# MicroCurrent.net
KiCad netlist of a schematic drawn in Altium Designer
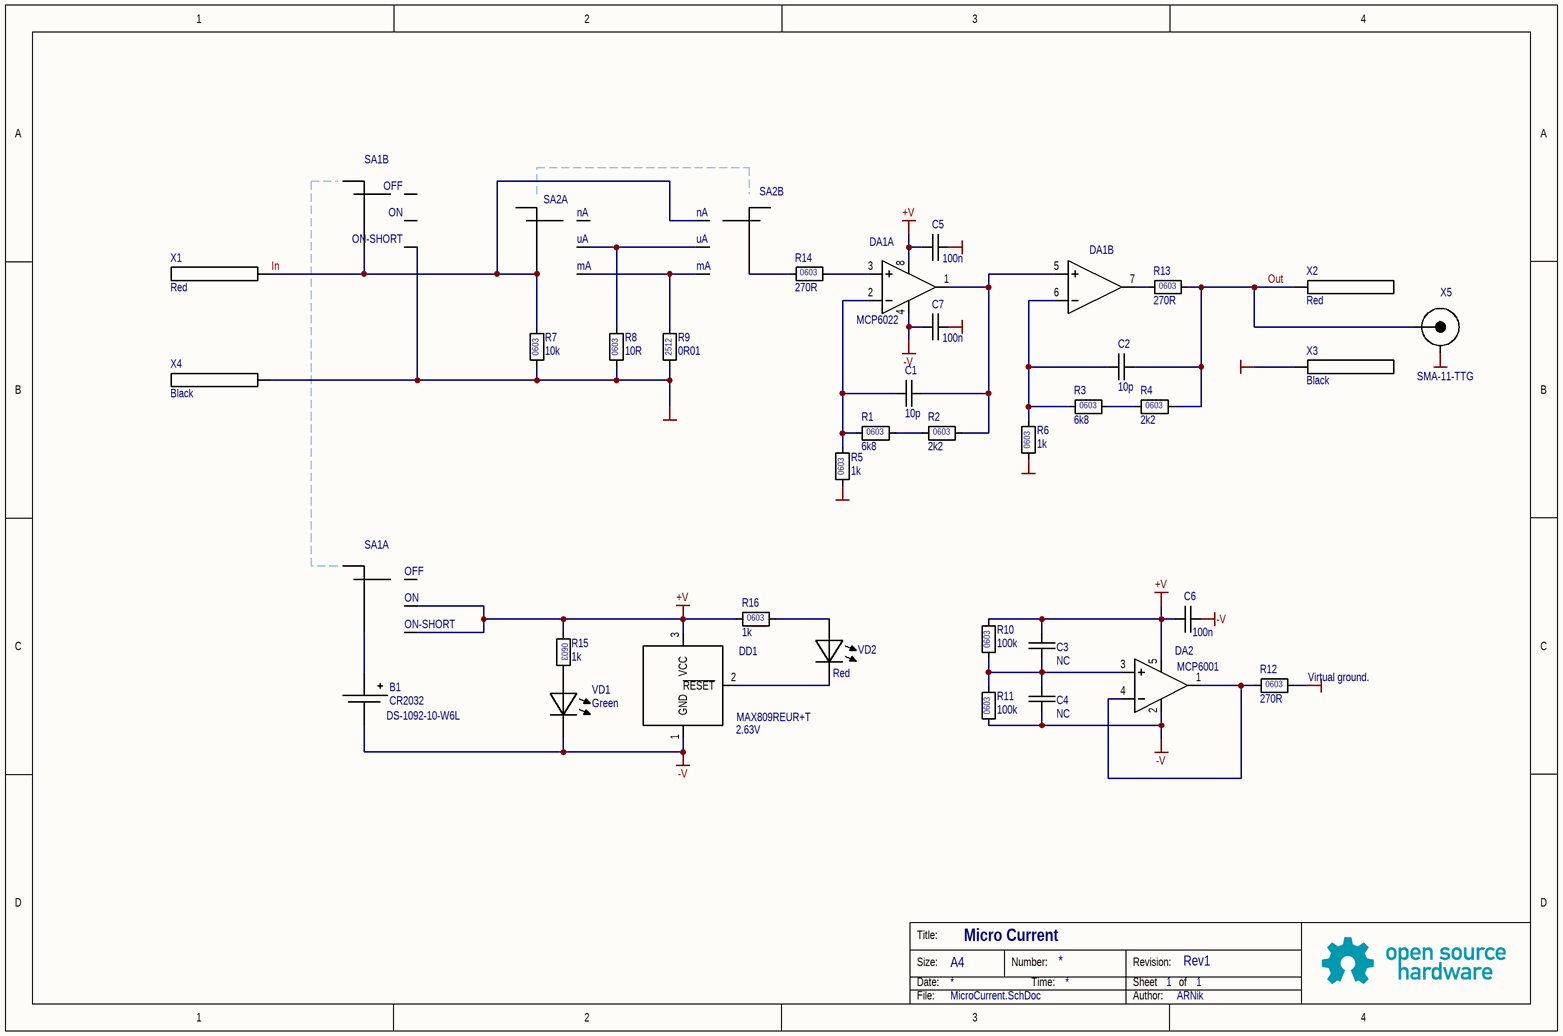
[diagram p0: MicroCurrent.SchDoc]

(export (version "E")
  (design (tool "Eeschema 10.0.6"))
  (components
    (comp (ref "B1")
      (value "CR2032")
      (footprint "DS1092-10-W6L")
      (description "CR2032 SMD battery holder")
      (fields (field (name "PART NUMBER") "DS-1092-10-W6L"))
      (libsource (lib "altium") (part "DS1092-10-W6L"))
    )
    (comp (ref "C1")
      (value "10p")
      (footprint "C0603")
      (description "Commercial Grade Mid Voltage (100 to 630V) ceramic capacitor")
      (fields (field (name "PART NUMBER") "C1608C0G2A100D080AA") (field (name "VOLTAGE") "100V"))
      (libsource (lib "altium") (part "Capacitor"))
    )
    (comp (ref "C2")
      (value "10p")
      (footprint "C0603")
      (description "Commercial Grade Mid Voltage (100 to 630V) ceramic capacitor")
      (fields (field (name "PART NUMBER") "C1608C0G2A100D080AA") (field (name "VOLTAGE") "100V"))
      (libsource (lib "altium") (part "Capacitor"))
    )
    (comp (ref "C3")
      (value "NC")
      (footprint "C0603")
      (description "NC 0603 Capasitor")
      (libsource (lib "altium") (part "Capacitor NB"))
    )
    (comp (ref "C4")
      (value "NC")
      (footprint "C0603")
      (description "NC 0603 Capasitor")
      (libsource (lib "altium") (part "Capacitor NB"))
    )
    (comp (ref "C5")
      (value "100n")
      (footprint "C0603")
      (description "General  ceramic capacitor")
      (fields (field (name "PART NUMBER") "GRM188R72A104MA35#") (field (name "VOLTAGE") "100V"))
      (libsource (lib "altium") (part "Capacitor"))
    )
    (comp (ref "C6")
      (value "100n")
      (footprint "C0603")
      (description "General  ceramic capacitor")
      (fields (field (name "PART NUMBER") "GRM188R72A104MA35#") (field (name "VOLTAGE") "100V"))
      (libsource (lib "altium") (part "Capacitor"))
    )
    (comp (ref "C7")
      (value "100n")
      (footprint "C0603")
      (description "General  ceramic capacitor")
      (fields (field (name "PART NUMBER") "GRM188R72A104MA35#") (field (name "VOLTAGE") "100V"))
      (libsource (lib "altium") (part "Capacitor"))
    )
    (comp (ref "DA1")
      (value "MCP6022")
      (footprint "Microchip-SOIC8 SN")
      (description "OpAmp Low offset Low Vcc")
      (fields (field (name "PART NUMBER") "MCP6022x"))
      (libsource (lib "altium") (part "MCP6022"))
    )
    (comp (ref "DA2")
      (value "MCP6001")
      (footprint "MICROCHIP-SOT-23-5 OT")
      (description "Low-Power Op Amp")
      (fields (field (name "PART NUMBER") "MCP6001xI OT"))
      (libsource (lib "altium") (part "MCP6001"))
    )
    (comp (ref "DD1")
      (value "2.63V")
      (footprint "MAXIM-SOT23-3L")
      (description "Microprocessor Reset Circuit")
      (fields (field (name "PART NUMBER") "MAX809REUR+T"))
      (libsource (lib "altium") (part "MAX803/803/810"))
    )
    (comp (ref "R1")
      (value "6k8")
      (footprint "R0603")
      (description "Thick Film Chip Resistor - CR Series")
      (fields (field (name "PART NUMBER") "CR-03FL7---6k8") (field (name "ALT PART") "RTT036801FTH (Ralec)"))
      (libsource (lib "altium") (part "Resistor - 0603"))
    )
    (comp (ref "R2")
      (value "2k2")
      (footprint "R0603")
      (description "Thick Film Chip Resistor - CR Series")
      (fields (field (name "PART NUMBER") "CR-03FL7---2k2") (field (name "ALT PART") "RTT032201FTH (Ralec)"))
      (libsource (lib "altium") (part "Resistor - 0603"))
    )
    (comp (ref "R3")
      (value "6k8")
      (footprint "R0603")
      (description "Thick Film Chip Resistor - CR Series")
      (fields (field (name "PART NUMBER") "CR-03FL7---6k8") (field (name "ALT PART") "RTT036801FTH (Ralec)"))
      (libsource (lib "altium") (part "Resistor - 0603"))
    )
    (comp (ref "R4")
      (value "2k2")
      (footprint "R0603")
      (description "Thick Film Chip Resistor - CR Series")
      (fields (field (name "PART NUMBER") "CR-03FL7---2k2") (field (name "ALT PART") "RTT032201FTH (Ralec)"))
      (libsource (lib "altium") (part "Resistor - 0603"))
    )
    (comp (ref "R5")
      (value "1k")
      (footprint "R0603")
      (description "Thick Film Chip Resistor - CR Series")
      (fields (field (name "PART NUMBER") "CR-03FL7----1k") (field (name "ALT PART") "RTT031001FTH (Ralec)"))
      (libsource (lib "altium") (part "Resistor - 0603"))
    )
    (comp (ref "R6")
      (value "1k")
      (footprint "R0603")
      (description "Thick Film Chip Resistor - CR Series")
      (fields (field (name "PART NUMBER") "CR-03FL7----1k") (field (name "ALT PART") "RTT031001FTH (Ralec)"))
      (libsource (lib "altium") (part "Resistor - 0603"))
    )
    (comp (ref "R7")
      (value "10k")
      (footprint "R0603")
      (description "Thick Film Chip Resistor - CR Series")
      (fields (field (name "PART NUMBER") "CR-03FL7---10k") (field (name "ALT PART") "RTT031002FTH (Ralec)"))
      (libsource (lib "altium") (part "Resistor - 0603"))
    )
    (comp (ref "R8")
      (value "10R")
      (footprint "R0603")
      (description "Thick Film Chip Resistor - CR Series")
      (fields (field (name "PART NUMBER") "CR-03FL7---10R") (field (name "ALT PART") "RTT03100FTH (Ralec)"))
      (libsource (lib "altium") (part "Resistor - 0603"))
    )
    (comp (ref "R9")
      (value "0R01")
      (footprint "R2512")
      (description "Thick Film Chip Resistor - CR Series")
      (fields (field (name "PART NUMBER") "CR-12FL4----1R") (field (name "ALT PART") "RTT251R0FTH (Ralec)"))
      (libsource (lib "altium") (part "Resistor - 2512"))
    )
    (comp (ref "R10")
      (value "100k")
      (footprint "R0603")
      (description "Thick Film Chip Resistor - CR Series")
      (fields (field (name "PART NUMBER") "CR-03FL7--100k") (field (name "ALT PART") "RTT031003FTH (Ralec)"))
      (libsource (lib "altium") (part "Resistor - 0603"))
    )
    (comp (ref "R11")
      (value "100k")
      (footprint "R0603")
      (description "Thick Film Chip Resistor - CR Series")
      (fields (field (name "PART NUMBER") "CR-03FL7--100k") (field (name "ALT PART") "RTT031003FTH (Ralec)"))
      (libsource (lib "altium") (part "Resistor - 0603"))
    )
    (comp (ref "R12")
      (value "270R")
      (footprint "R0603")
      (description "Thick Film Chip Resistor - CR Series")
      (fields (field (name "PART NUMBER") "CR-03FL7--270R") (field (name "ALT PART") "RTT032700FTH (Ralec)"))
      (libsource (lib "altium") (part "Resistor - 0603"))
    )
    (comp (ref "R13")
      (value "270R")
      (footprint "R0603")
      (description "Thick Film Chip Resistor - CR Series")
      (fields (field (name "PART NUMBER") "CR-03FL7--270R") (field (name "ALT PART") "RTT032700FTH (Ralec)"))
      (libsource (lib "altium") (part "Resistor - 0603"))
    )
    (comp (ref "R14")
      (value "270R")
      (footprint "R0603")
      (description "Thick Film Chip Resistor - CR Series")
      (fields (field (name "PART NUMBER") "CR-03FL7--270R") (field (name "ALT PART") "RTT032700FTH (Ralec)"))
      (libsource (lib "altium") (part "Resistor - 0603"))
    )
    (comp (ref "R15")
      (value "1k")
      (footprint "R0603")
      (description "Thick Film Chip Resistor - CR Series")
      (fields (field (name "PART NUMBER") "CR-03FL7----1k") (field (name "ALT PART") "RTT031001FTH (Ralec)"))
      (libsource (lib "altium") (part "Resistor - 0603"))
    )
    (comp (ref "R16")
      (value "1k")
      (footprint "R0603")
      (description "Thick Film Chip Resistor - CR Series")
      (fields (field (name "PART NUMBER") "CR-03FL7----1k") (field (name "ALT PART") "RTT031001FTH (Ralec)"))
      (libsource (lib "altium") (part "Resistor - 0603"))
    )
    (comp (ref "SA1") (value "~") (libsource (lib "Switches") (part "SS23D07")))
    (comp (ref "SA2") (value "~") (libsource (lib "Switches") (part "SS23D07")))
    (comp (ref "VD1")
      (value "Green")
      (footprint "LTST-C191 GREEN")
      (description "TopView Single Color Chip LED")
      (fields (field (name "PART NUMBER") "LTST-C191KGKT-5A"))
      (libsource (lib "altium") (part "LED"))
    )
    (comp (ref "VD2")
      (value "Red")
      (footprint "LTST-C193 RED")
      (description "TopView Single Color Chip LED")
      (fields (field (name "PART NUMBER") "LTST-C193KRKT-5A"))
      (libsource (lib "altium") (part "LED"))
    )
    (comp (ref "X1")
      (value "Red")
      (footprint "RTC5060185-red")
      (fields (field (name "PART NUMBER") "RTC5060185-red"))
      (libsource (lib "altium") (part "Connector-1"))
    )
    (comp (ref "X2")
      (value "Red")
      (footprint "RTC5060185-red")
      (fields (field (name "PART NUMBER") "RTC5060185-red"))
      (libsource (lib "altium") (part "Connector-1"))
    )
    (comp (ref "X3")
      (value "Black")
      (footprint "RTC5060185-black")
      (fields (field (name "PART NUMBER") "RTC5060185-black"))
      (libsource (lib "altium") (part "Connector-1"))
    )
    (comp (ref "X4")
      (value "Black")
      (footprint "RTC5060185-black")
      (fields (field (name "PART NUMBER") "RTC5060185-black"))
      (libsource (lib "altium") (part "Connector-1"))
    )
    (comp (ref "X5")
      (value "Connector HF")
      (footprint "SMA-11-TTG")
      (description "angle sma connector")
      (fields (field (name "PART NUMBER") "SMA-11-TTG"))
      (libsource (lib "altium") (part "Connector HF"))
    )
  )
  (nets
    (net (code "1") (name "+V") (class "Default")
      (node (ref "C3") (pin "1") (pinfunction "1_1") (pintype "passive"))
      (node (ref "C5") (pin "1") (pinfunction "1_1") (pintype "passive"))
      (node (ref "C6") (pin "2") (pinfunction "2_2") (pintype "passive"))
      (node (ref "DA1") (pin "8") (pinfunction "VCC_8") (pintype "passive"))
      (node (ref "DA2") (pin "5") (pinfunction "VCC_5") (pintype "passive"))
      (node (ref "DD1") (pin "3") (pinfunction "VCC_3") (pintype "passive"))
      (node (ref "R10") (pin "2") (pinfunction "2_2") (pintype "passive"))
      (node (ref "R15") (pin "1") (pinfunction "1_1") (pintype "passive"))
      (node (ref "R16") (pin "1") (pinfunction "1_1") (pintype "passive"))
      (node (ref "SA1") (pin "3.1") (pintype "passive"))
      (node (ref "SA1") (pin "4.1") (pintype "passive"))
    )
    (net (code "2") (name "-V") (class "Default")
      (node (ref "B1") (pin "2") (pintype "passive"))
      (node (ref "C4") (pin "2") (pinfunction "2_2") (pintype "passive"))
      (node (ref "C6") (pin "1") (pinfunction "1_1") (pintype "passive"))
      (node (ref "C7") (pin "1") (pinfunction "1_1") (pintype "passive"))
      (node (ref "DA1") (pin "4") (pinfunction "GND_4") (pintype "passive"))
      (node (ref "DA2") (pin "2") (pinfunction "GND_2") (pintype "passive"))
      (node (ref "DD1") (pin "1") (pinfunction "GND_1") (pintype "passive"))
      (node (ref "R11") (pin "1") (pinfunction "1_1") (pintype "passive"))
      (node (ref "VD1") (pin "1") (pinfunction "C_1") (pintype "passive"))
    )
    (net (code "3") (name "/In") (class "Default")
      (node (ref "R7") (pin "2") (pinfunction "2_2") (pintype "passive"))
      (node (ref "SA1") (pin "2.2") (pintype "passive"))
      (node (ref "SA2") (pin "1.2") (pintype "passive"))
      (node (ref "SA2") (pin "2.1") (pintype "passive"))
      (node (ref "X1") (pin "1") (pintype "passive"))
    )
    (net (code "4") (name "/Out") (class "Default")
      (node (ref "C2") (pin "2") (pinfunction "2_2") (pintype "passive"))
      (node (ref "R13") (pin "2") (pinfunction "2_2") (pintype "passive"))
      (node (ref "R4") (pin "2") (pinfunction "2_2") (pintype "passive"))
      (node (ref "X2") (pin "1") (pintype "passive"))
      (node (ref "X5") (pin "1") (pintype "passive"))
    )
    (net (code "5") (name "GND") (class "Default")
      (node (ref "C5") (pin "2") (pinfunction "2_2") (pintype "passive"))
      (node (ref "C7") (pin "2") (pinfunction "2_2") (pintype "passive"))
      (node (ref "R12") (pin "2") (pinfunction "2_2") (pintype "passive"))
      (node (ref "R5") (pin "1") (pinfunction "1_1") (pintype "passive"))
      (node (ref "R6") (pin "1") (pinfunction "1_1") (pintype "passive"))
      (node (ref "R7") (pin "1") (pinfunction "1_1") (pintype "passive"))
      (node (ref "R8") (pin "1") (pinfunction "1_1") (pintype "passive"))
      (node (ref "R9") (pin "1") (pinfunction "1_1") (pintype "passive"))
      (node (ref "SA1") (pin "4.2") (pintype "passive"))
      (node (ref "X3") (pin "1") (pintype "passive"))
      (node (ref "X4") (pin "1") (pintype "passive"))
      (node (ref "X5") (pin "2") (pintype "passive"))
    )
    (net (code "6") (name "Net-(B1-Pad1)") (class "Default")
      (node (ref "B1") (pin "1") (pintype "passive"))
      (node (ref "SA1") (pin "2.1") (pintype "passive"))
    )
    (net (code "7") (name "Net-(DA1A-1IN+)") (class "Default")
      (node (ref "DA1") (pin "3") (pinfunction "1IN+_3") (pintype "passive"))
      (node (ref "R14") (pin "2") (pinfunction "2_2") (pintype "passive"))
    )
    (net (code "8") (name "Net-(DA1A-1IN-)") (class "Default")
      (node (ref "C1") (pin "1") (pinfunction "1_1") (pintype "passive"))
      (node (ref "DA1") (pin "2") (pinfunction "1IN-_2") (pintype "passive"))
      (node (ref "R1") (pin "1") (pinfunction "1_1") (pintype "passive"))
      (node (ref "R5") (pin "2") (pinfunction "2_2") (pintype "passive"))
    )
    (net (code "9") (name "Net-(DA1A-1OUT)") (class "Default")
      (node (ref "C1") (pin "2") (pinfunction "2_2") (pintype "passive"))
      (node (ref "DA1") (pin "1") (pinfunction "1OUT_1") (pintype "passive"))
      (node (ref "DA1") (pin "5") (pinfunction "2IN+_5") (pintype "passive"))
      (node (ref "R2") (pin "2") (pinfunction "2_2") (pintype "passive"))
    )
    (net (code "10") (name "Net-(DA1B-2IN-)") (class "Default")
      (node (ref "C2") (pin "1") (pinfunction "1_1") (pintype "passive"))
      (node (ref "DA1") (pin "6") (pinfunction "2IN-_6") (pintype "passive"))
      (node (ref "R3") (pin "1") (pinfunction "1_1") (pintype "passive"))
      (node (ref "R6") (pin "2") (pinfunction "2_2") (pintype "passive"))
    )
    (net (code "11") (name "Net-(DA1B-2OUT)") (class "Default")
      (node (ref "DA1") (pin "7") (pinfunction "2OUT_7") (pintype "passive"))
      (node (ref "R13") (pin "1") (pinfunction "1_1") (pintype "passive"))
    )
    (net (code "12") (name "Net-(DA2-1IN+)") (class "Default")
      (node (ref "C3") (pin "2") (pinfunction "2_2") (pintype "passive"))
      (node (ref "C4") (pin "1") (pinfunction "1_1") (pintype "passive"))
      (node (ref "DA2") (pin "3") (pinfunction "1IN+_3") (pintype "passive"))
      (node (ref "R10") (pin "1") (pinfunction "1_1") (pintype "passive"))
      (node (ref "R11") (pin "2") (pinfunction "2_2") (pintype "passive"))
    )
    (net (code "13") (name "Net-(DA2-1IN-)") (class "Default")
      (node (ref "DA2") (pin "1") (pinfunction "1OUT_1") (pintype "passive"))
      (node (ref "DA2") (pin "4") (pinfunction "1IN-_4") (pintype "passive"))
      (node (ref "R12") (pin "1") (pinfunction "1_1") (pintype "passive"))
    )
    (net (code "14") (name "Net-(DD1-~{RESET})") (class "Default")
      (node (ref "DD1") (pin "2") (pinfunction "~{RESET}_2") (pintype "passive"))
      (node (ref "VD2") (pin "1") (pinfunction "C_1") (pintype "passive"))
    )
    (net (code "15") (name "Net-(R1-Pad2)") (class "Default")
      (node (ref "R1") (pin "2") (pinfunction "2_2") (pintype "passive"))
      (node (ref "R2") (pin "1") (pinfunction "1_1") (pintype "passive"))
    )
    (net (code "16") (name "Net-(R3-Pad2)") (class "Default")
      (node (ref "R3") (pin "2") (pinfunction "2_2") (pintype "passive"))
      (node (ref "R4") (pin "1") (pinfunction "1_1") (pintype "passive"))
    )
    (net (code "17") (name "Net-(R8-Pad2)") (class "Default")
      (node (ref "R8") (pin "2") (pinfunction "2_2") (pintype "passive"))
      (node (ref "SA2") (pin "3.1") (pintype "passive"))
      (node (ref "SA2") (pin "3.2") (pintype "passive"))
    )
    (net (code "18") (name "Net-(R9-Pad2)") (class "Default")
      (node (ref "R9") (pin "2") (pinfunction "2_2") (pintype "passive"))
      (node (ref "SA2") (pin "4.1") (pintype "passive"))
      (node (ref "SA2") (pin "4.2") (pintype "passive"))
    )
    (net (code "19") (name "Net-(R14-Pad1)") (class "Default")
      (node (ref "R14") (pin "1") (pinfunction "1_1") (pintype "passive"))
      (node (ref "SA2") (pin "2.2") (pintype "passive"))
    )
    (net (code "20") (name "Net-(VD1-A)") (class "Default")
      (node (ref "R15") (pin "2") (pinfunction "2_2") (pintype "passive"))
      (node (ref "VD1") (pin "2") (pinfunction "A_2") (pintype "passive"))
    )
    (net (code "21") (name "Net-(VD2-A)") (class "Default")
      (node (ref "R16") (pin "2") (pinfunction "2_2") (pintype "passive"))
      (node (ref "VD2") (pin "2") (pinfunction "A_2") (pintype "passive"))
    )
    (net (code "22") (name "unconnected-(SA1-Pad1.1)") (class "Default")
      (node (ref "SA1") (pin "1.1") (pintype "passive"))
    )
    (net (code "23") (name "unconnected-(SA1-Pad1.2)") (class "Default")
      (node (ref "SA1") (pin "1.2") (pintype "passive"))
    )
    (net (code "24") (name "unconnected-(SA1-Pad3.2)") (class "Default")
      (node (ref "SA1") (pin "3.2") (pintype "passive"))
    )
    (net (code "25") (name "unconnected-(SA2-Pad1.1)") (class "Default")
      (node (ref "SA2") (pin "1.1") (pintype "passive"))
    )
  )
)
